# fuel_injectorREVB.net
KiCad netlist of a schematic drawn in EAGLE
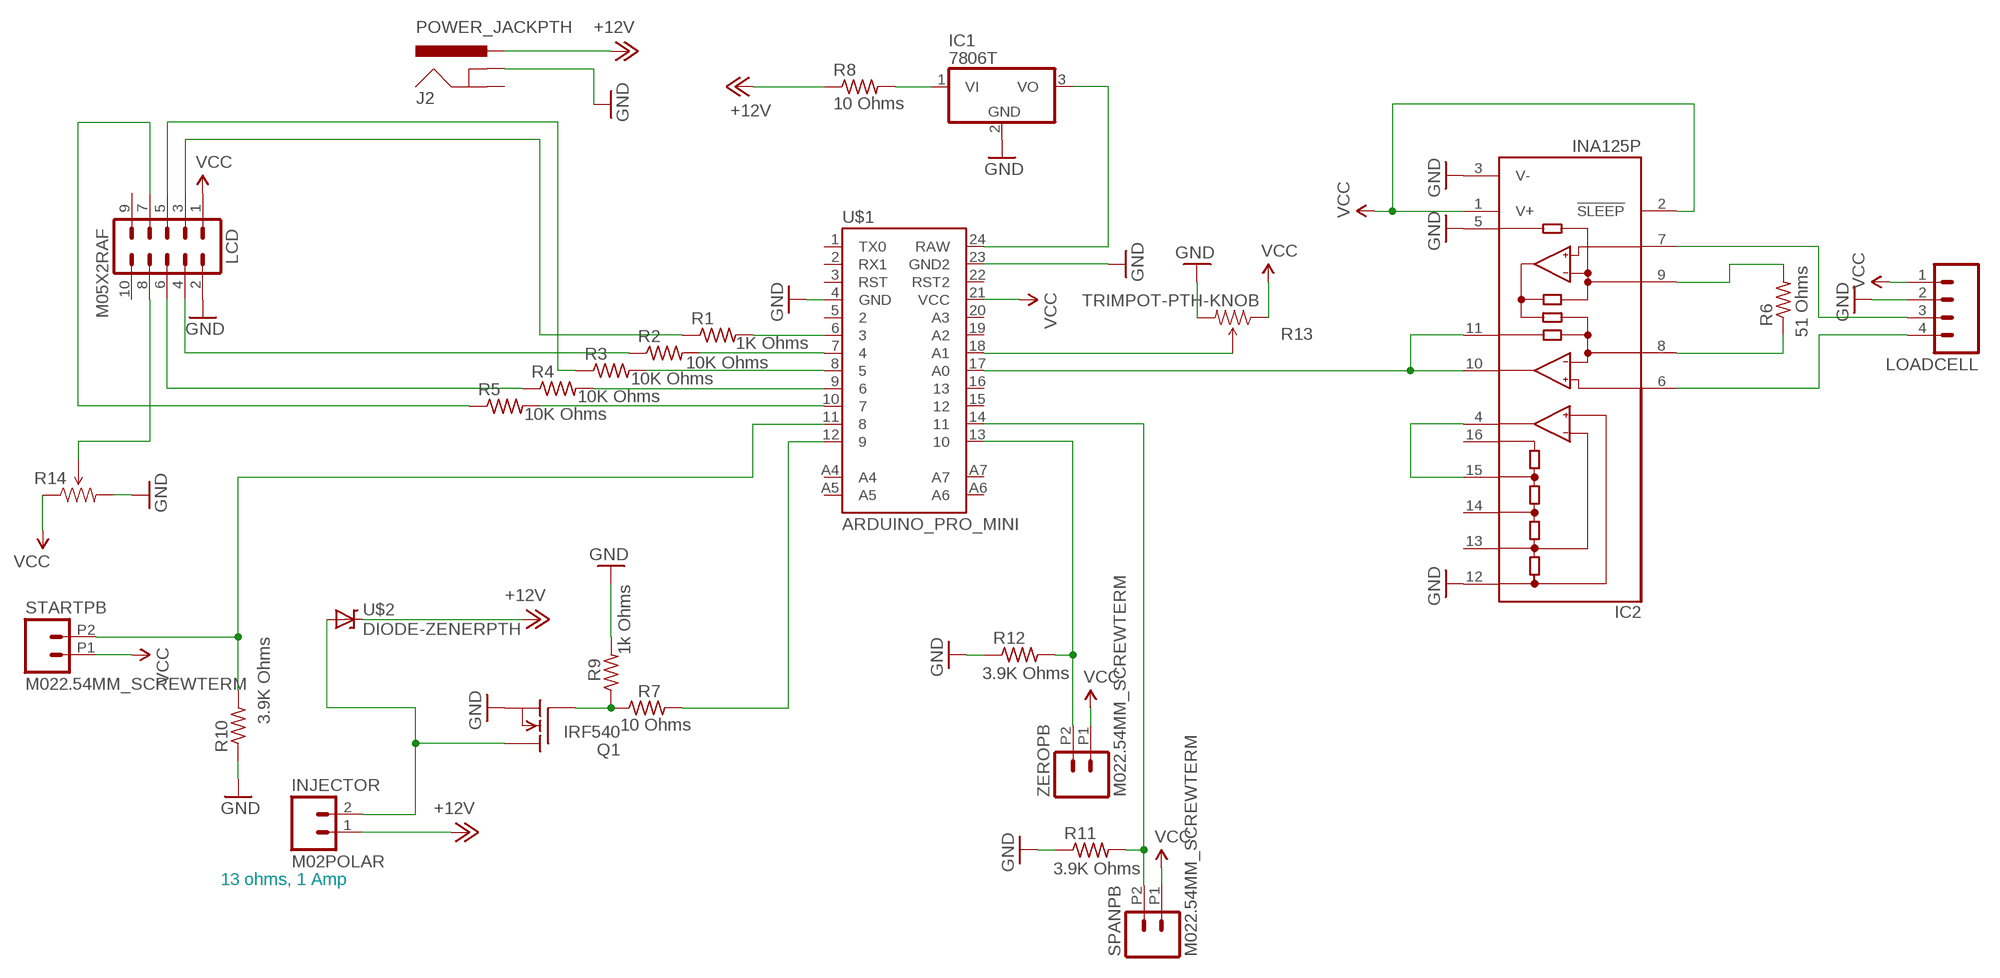
[diagram p0: schematic, sheet 1]

(export (version "E")
  (design (tool "Eeschema 10.0.6"))
  (components
    (comp (ref "IC1")
      (value "7806T")
      (footprint "eagle-import:TO220H")
      (libsource (lib "eagle-import") (part "78T06"))
    )
    (comp (ref "IC2")
      (value "INA125P")
      (footprint "eagle-import:DIL16")
      (fields (field (name "MF") "TEXAS INSTRUMENT CONNECTORS"))
      (libsource (lib "eagle-import") (part "INA125P"))
    )
    (comp (ref "INJECTOR")
      (value "M02POLAR")
      (footprint "eagle-import:MOLEX-1X2")
      (libsource (lib "eagle-import") (part "M02POLAR"))
    )
    (comp (ref "J2")
      (value "POWER_JACKPTH")
      (footprint "eagle-import:POWER_JACK_PTH")
      (libsource (lib "eagle-import") (part "POWER_JACKPTH"))
    )
    (comp (ref "LCD")
      (value "M05X2RAF")
      (footprint "eagle-import:2X5-RAF")
      (libsource (lib "eagle-import") (part "M05X2RAF"))
    )
    (comp (ref "LOADCELL")
      (value "M04POLAR")
      (footprint "eagle-import:MOLEX-1X4")
      (libsource (lib "eagle-import") (part "M04POLAR"))
    )
    (comp (ref "Q1")
      (value "IRF540")
      (footprint "eagle-import:TO220")
      (libsource (lib "eagle-import") (part "IRF540"))
    )
    (comp (ref "R1")
      (value "1K Ohms")
      (footprint "eagle-import:0309_10")
      (libsource (lib "eagle-import") (part "resistor_R-US_0309/10"))
    )
    (comp (ref "R2")
      (value "10K Ohms")
      (footprint "eagle-import:0309_10")
      (libsource (lib "eagle-import") (part "resistor_R-US_0309/10"))
    )
    (comp (ref "R3")
      (value "10K Ohms")
      (footprint "eagle-import:0309_10")
      (libsource (lib "eagle-import") (part "resistor_R-US_0309/10"))
    )
    (comp (ref "R4")
      (value "10K Ohms")
      (footprint "eagle-import:0309_10")
      (libsource (lib "eagle-import") (part "resistor_R-US_0309/10"))
    )
    (comp (ref "R5")
      (value "10K Ohms")
      (footprint "eagle-import:0309_10")
      (libsource (lib "eagle-import") (part "resistor_R-US_0309/10"))
    )
    (comp (ref "R6")
      (value "51 Ohms")
      (footprint "eagle-import:0309_10")
      (libsource (lib "eagle-import") (part "resistor_R-US_0309/10"))
    )
    (comp (ref "R7")
      (value "10 Ohms")
      (footprint "eagle-import:0207_15")
      (libsource (lib "eagle-import") (part "resistor_R-US_0207/15"))
    )
    (comp (ref "R8")
      (value "10 Ohms")
      (footprint "eagle-import:P0613_15")
      (libsource (lib "eagle-import") (part "R-US_0613/15"))
    )
    (comp (ref "R9")
      (value "1k Ohms")
      (footprint "eagle-import:0309_10")
      (libsource (lib "eagle-import") (part "resistor_R-US_0309/10"))
    )
    (comp (ref "R10")
      (value "3.9K Ohms")
      (footprint "eagle-import:0309_10")
      (libsource (lib "eagle-import") (part "resistor_R-US_0309/10"))
    )
    (comp (ref "R11")
      (value "3.9K Ohms")
      (footprint "eagle-import:0309_10")
      (libsource (lib "eagle-import") (part "resistor_R-US_0309/10"))
    )
    (comp (ref "R12")
      (value "3.9K Ohms")
      (footprint "eagle-import:0309_10")
      (libsource (lib "eagle-import") (part "resistor_R-US_0309/10"))
    )
    (comp (ref "R13")
      (value "TRIMPOT-PTH-KNOB")
      (footprint "eagle-import:3386U")
      (libsource (lib "eagle-import") (part "TRIMPOT-PTH-KNOB"))
    )
    (comp (ref "R14")
      (value "TRIMPOT-PTH-KNOB")
      (footprint "eagle-import:3386U")
      (libsource (lib "eagle-import") (part "TRIMPOT-PTH-KNOB"))
    )
    (comp (ref "SPANPB")
      (value "M022.54MM_SCREWTERM")
      (footprint "eagle-import:1X02_2.54_SCREWTERM")
      (libsource (lib "eagle-import") (part "M022.54MM_SCREWTERM"))
    )
    (comp (ref "STARTPB")
      (value "M022.54MM_SCREWTERM")
      (footprint "eagle-import:1X02_2.54_SCREWTERM")
      (libsource (lib "eagle-import") (part "M022.54MM_SCREWTERM"))
    )
    (comp (ref "U$1")
      (value "ARDUINO_PRO_MINI")
      (footprint "eagle-import:ARDUINO_PRO_MINI")
      (libsource (lib "eagle-import") (part "ARDUINO_PRO_MINI"))
    )
    (comp (ref "U$2")
      (value "DIODE-ZENERPTH")
      (footprint "eagle-import:DIODE-ZENER")
      (libsource (lib "eagle-import") (part "DIODE-ZENERPTH"))
    )
    (comp (ref "ZEROPB")
      (value "M022.54MM_SCREWTERM")
      (footprint "eagle-import:1X02_2.54_SCREWTERM")
      (libsource (lib "eagle-import") (part "M022.54MM_SCREWTERM"))
    )
  )
  (nets
    (net (code "1") (name "+12V") (class "Default")
      (node (ref "INJECTOR") (pin "1") (pinfunction "1_1") (pintype "passive"))
      (node (ref "J2") (pin "PWR") (pinfunction "PWR_PWR") (pintype "bidirectional"))
      (node (ref "R8") (pin "1") (pinfunction "1_1") (pintype "passive"))
      (node (ref "U$2") (pin "P$1") (pinfunction "C_P$1") (pintype "passive"))
    )
    (net (code "2") (name "GND") (class "Default")
      (node (ref "IC1") (pin "2") (pinfunction "GND_2") (pintype "passive"))
      (node (ref "IC2") (pin "12") (pinfunction "REFCOM_12") (pintype "passive"))
      (node (ref "IC2") (pin "3") (pinfunction "V-_3") (pintype "power_in"))
      (node (ref "IC2") (pin "5") (pinfunction "REF_5") (pintype "passive"))
      (node (ref "J2") (pin "GNDBREAK") (pinfunction "GNDBREAK_GNDBREAK") (pintype "bidirectional"))
      (node (ref "LCD") (pin "2") (pinfunction "2_2") (pintype "passive"))
      (node (ref "LOADCELL") (pin "2") (pinfunction "2_2") (pintype "passive"))
      (node (ref "Q1") (pin "3") (pinfunction "S_3") (pintype "passive"))
      (node (ref "R10") (pin "1") (pinfunction "1_1") (pintype "passive"))
      (node (ref "R11") (pin "1") (pinfunction "1_1") (pintype "passive"))
      (node (ref "R12") (pin "1") (pinfunction "1_1") (pintype "passive"))
      (node (ref "R13") (pin "3") (pinfunction "CW_3") (pintype "passive"))
      (node (ref "R14") (pin "3") (pinfunction "CW_3") (pintype "passive"))
      (node (ref "R9") (pin "2") (pinfunction "2_2") (pintype "passive"))
      (node (ref "U$1") (pin "23") (pinfunction "GND2_23") (pintype "bidirectional"))
      (node (ref "U$1") (pin "4") (pinfunction "GND_4") (pintype "bidirectional"))
    )
    (net (code "3") (name "Net-(IC1-VI)") (class "Default")
      (node (ref "IC1") (pin "1") (pinfunction "VI_1") (pintype "input"))
      (node (ref "R8") (pin "2") (pinfunction "2_2") (pintype "passive"))
    )
    (net (code "4") (name "Net-(IC1-VO)") (class "Default")
      (node (ref "IC1") (pin "3") (pinfunction "VO_3") (pintype "passive"))
      (node (ref "U$1") (pin "24") (pinfunction "RAW_24") (pintype "bidirectional"))
    )
    (net (code "5") (name "Net-(IC2-+IN)") (class "Default")
      (node (ref "IC2") (pin "6") (pinfunction "+IN_6") (pintype "input"))
      (node (ref "LOADCELL") (pin "4") (pinfunction "4_4") (pintype "passive"))
    )
    (net (code "6") (name "Net-(IC2--IN)") (class "Default")
      (node (ref "IC2") (pin "7") (pinfunction "-IN_7") (pintype "input"))
      (node (ref "LOADCELL") (pin "3") (pinfunction "3_3") (pintype "passive"))
    )
    (net (code "7") (name "Net-(IC2-OUT)") (class "Default")
      (node (ref "IC2") (pin "10") (pinfunction "OUT_10") (pintype "output"))
      (node (ref "IC2") (pin "11") (pinfunction "SENSE_11") (pintype "passive"))
      (node (ref "U$1") (pin "17") (pinfunction "A0_17") (pintype "bidirectional"))
    )
    (net (code "8") (name "Net-(IC2-REF5)") (class "Default")
      (node (ref "IC2") (pin "15") (pinfunction "REF5_15") (pintype "output"))
      (node (ref "IC2") (pin "4") (pinfunction "REFOUT_4") (pintype "output"))
    )
    (net (code "9") (name "Net-(IC2-RG-Pad8)") (class "Default")
      (node (ref "IC2") (pin "8") (pinfunction "RG_8") (pintype "passive"))
      (node (ref "R6") (pin "1") (pinfunction "1_1") (pintype "passive"))
    )
    (net (code "10") (name "Net-(IC2-RG-Pad9)") (class "Default")
      (node (ref "IC2") (pin "9") (pinfunction "RG_9") (pintype "passive"))
      (node (ref "R6") (pin "2") (pinfunction "2_2") (pintype "passive"))
    )
    (net (code "11") (name "Net-(LCD-Pad3)") (class "Default")
      (node (ref "LCD") (pin "3") (pinfunction "3_3") (pintype "passive"))
      (node (ref "R1") (pin "1") (pinfunction "1_1") (pintype "passive"))
    )
    (net (code "12") (name "Net-(LCD-Pad4)") (class "Default")
      (node (ref "LCD") (pin "4") (pinfunction "4_4") (pintype "passive"))
      (node (ref "R2") (pin "1") (pinfunction "1_1") (pintype "passive"))
    )
    (net (code "13") (name "Net-(LCD-Pad5)") (class "Default")
      (node (ref "LCD") (pin "5") (pinfunction "5_5") (pintype "passive"))
      (node (ref "R3") (pin "1") (pinfunction "1_1") (pintype "passive"))
    )
    (net (code "14") (name "Net-(LCD-Pad6)") (class "Default")
      (node (ref "LCD") (pin "6") (pinfunction "6_6") (pintype "passive"))
      (node (ref "R4") (pin "1") (pinfunction "1_1") (pintype "passive"))
    )
    (net (code "15") (name "Net-(LCD-Pad7)") (class "Default")
      (node (ref "LCD") (pin "7") (pinfunction "7_7") (pintype "passive"))
      (node (ref "R5") (pin "1") (pinfunction "1_1") (pintype "passive"))
    )
    (net (code "16") (name "Net-(Q1-D)") (class "Default")
      (node (ref "INJECTOR") (pin "2") (pinfunction "2_2") (pintype "passive"))
      (node (ref "Q1") (pin "2") (pinfunction "D_2") (pintype "passive"))
      (node (ref "U$2") (pin "P$2") (pinfunction "A_P$2") (pintype "passive"))
    )
    (net (code "17") (name "Net-(Q1-G)") (class "Default")
      (node (ref "Q1") (pin "1") (pinfunction "G_1") (pintype "passive"))
      (node (ref "R7") (pin "1") (pinfunction "1_1") (pintype "passive"))
      (node (ref "R9") (pin "1") (pinfunction "1_1") (pintype "passive"))
    )
    (net (code "18") (name "Net-(R13-WIPER)") (class "Default")
      (node (ref "R13") (pin "2") (pinfunction "WIPER_2") (pintype "passive"))
      (node (ref "U$1") (pin "18") (pinfunction "A1_18") (pintype "bidirectional"))
    )
    (net (code "19") (name "Net-(R14-WIPER)") (class "Default")
      (node (ref "LCD") (pin "8") (pinfunction "8_8") (pintype "passive"))
      (node (ref "R14") (pin "2") (pinfunction "WIPER_2") (pintype "passive"))
    )
    (net (code "20") (name "Net-(SPANPB-2)") (class "Default")
      (node (ref "R11") (pin "2") (pinfunction "2_2") (pintype "passive"))
      (node (ref "SPANPB") (pin "P2") (pinfunction "2_P2") (pintype "passive"))
      (node (ref "U$1") (pin "14") (pinfunction "11_14") (pintype "bidirectional"))
    )
    (net (code "21") (name "Net-(STARTPB-2)") (class "Default")
      (node (ref "R10") (pin "2") (pinfunction "2_2") (pintype "passive"))
      (node (ref "STARTPB") (pin "P2") (pinfunction "2_P2") (pintype "passive"))
      (node (ref "U$1") (pin "11") (pinfunction "8_11") (pintype "bidirectional"))
    )
    (net (code "22") (name "Net-(U$1-3)") (class "Default")
      (node (ref "R1") (pin "2") (pinfunction "2_2") (pintype "passive"))
      (node (ref "U$1") (pin "6") (pinfunction "3_6") (pintype "bidirectional"))
    )
    (net (code "23") (name "Net-(U$1-4)") (class "Default")
      (node (ref "R2") (pin "2") (pinfunction "2_2") (pintype "passive"))
      (node (ref "U$1") (pin "7") (pinfunction "4_7") (pintype "bidirectional"))
    )
    (net (code "24") (name "Net-(U$1-5)") (class "Default")
      (node (ref "R3") (pin "2") (pinfunction "2_2") (pintype "passive"))
      (node (ref "U$1") (pin "8") (pinfunction "5_8") (pintype "bidirectional"))
    )
    (net (code "25") (name "Net-(U$1-6)") (class "Default")
      (node (ref "R4") (pin "2") (pinfunction "2_2") (pintype "passive"))
      (node (ref "U$1") (pin "9") (pinfunction "6_9") (pintype "bidirectional"))
    )
    (net (code "26") (name "Net-(U$1-7)") (class "Default")
      (node (ref "R5") (pin "2") (pinfunction "2_2") (pintype "passive"))
      (node (ref "U$1") (pin "10") (pinfunction "7_10") (pintype "bidirectional"))
    )
    (net (code "27") (name "Net-(U$1-9)") (class "Default")
      (node (ref "R7") (pin "2") (pinfunction "2_2") (pintype "passive"))
      (node (ref "U$1") (pin "12") (pinfunction "9_12") (pintype "bidirectional"))
    )
    (net (code "28") (name "Net-(U$1-10)") (class "Default")
      (node (ref "R12") (pin "2") (pinfunction "2_2") (pintype "passive"))
      (node (ref "U$1") (pin "13") (pinfunction "10_13") (pintype "bidirectional"))
      (node (ref "ZEROPB") (pin "P2") (pinfunction "2_P2") (pintype "passive"))
    )
    (net (code "29") (name "VCC") (class "Default")
      (node (ref "IC2") (pin "1") (pinfunction "V+_1") (pintype "power_in"))
      (node (ref "IC2") (pin "2") (pinfunction "~{SLEEP}_2") (pintype "input"))
      (node (ref "LCD") (pin "1") (pinfunction "1_1") (pintype "passive"))
      (node (ref "LOADCELL") (pin "1") (pinfunction "1_1") (pintype "passive"))
      (node (ref "R13") (pin "1") (pinfunction "CCW_1") (pintype "passive"))
      (node (ref "R14") (pin "1") (pinfunction "CCW_1") (pintype "passive"))
      (node (ref "SPANPB") (pin "P1") (pinfunction "1_P1") (pintype "passive"))
      (node (ref "STARTPB") (pin "P1") (pinfunction "1_P1") (pintype "passive"))
      (node (ref "U$1") (pin "21") (pinfunction "VCC_21") (pintype "bidirectional"))
      (node (ref "ZEROPB") (pin "P1") (pinfunction "1_P1") (pintype "passive"))
    )
    (net (code "30") (name "unconnected-(IC2-REF2.5-Pad14)") (class "Default")
      (node (ref "IC2") (pin "14") (pinfunction "REF2.5_14") (pintype "output"))
    )
    (net (code "31") (name "unconnected-(IC2-REF10-Pad16)") (class "Default")
      (node (ref "IC2") (pin "16") (pinfunction "REF10_16") (pintype "output"))
    )
    (net (code "32") (name "unconnected-(IC2-REFBG-Pad13)") (class "Default")
      (node (ref "IC2") (pin "13") (pinfunction "REFBG_13") (pintype "output"))
    )
    (net (code "33") (name "unconnected-(J2-PadGND)") (class "Default")
      (node (ref "J2") (pin "GND") (pinfunction "GND_GND") (pintype "bidirectional"))
    )
    (net (code "34") (name "unconnected-(LCD-Pad9)") (class "Default")
      (node (ref "LCD") (pin "9") (pinfunction "9_9") (pintype "passive"))
    )
    (net (code "35") (name "unconnected-(LCD-Pad10)") (class "Default")
      (node (ref "LCD") (pin "10") (pinfunction "10_10") (pintype "passive"))
    )
    (net (code "36") (name "unconnected-(U$1-2-Pad5)") (class "Default")
      (node (ref "U$1") (pin "5") (pinfunction "2_5") (pintype "bidirectional"))
    )
    (net (code "37") (name "unconnected-(U$1-12-Pad15)") (class "Default")
      (node (ref "U$1") (pin "15") (pinfunction "12_15") (pintype "bidirectional"))
    )
    (net (code "38") (name "unconnected-(U$1-13-Pad16)") (class "Default")
      (node (ref "U$1") (pin "16") (pinfunction "13_16") (pintype "bidirectional"))
    )
    (net (code "39") (name "unconnected-(U$1-A2-Pad19)") (class "Default")
      (node (ref "U$1") (pin "19") (pinfunction "A2_19") (pintype "bidirectional"))
    )
    (net (code "40") (name "unconnected-(U$1-A3-Pad20)") (class "Default")
      (node (ref "U$1") (pin "20") (pinfunction "A3_20") (pintype "bidirectional"))
    )
    (net (code "41") (name "unconnected-(U$1-PadA4)") (class "Default")
      (node (ref "U$1") (pin "A4") (pinfunction "A4_A4") (pintype "bidirectional"))
    )
    (net (code "42") (name "unconnected-(U$1-PadA5)") (class "Default")
      (node (ref "U$1") (pin "A5") (pinfunction "A5_A5") (pintype "bidirectional"))
    )
    (net (code "43") (name "unconnected-(U$1-PadA6)") (class "Default")
      (node (ref "U$1") (pin "A6") (pinfunction "A6_A6") (pintype "bidirectional"))
    )
    (net (code "44") (name "unconnected-(U$1-PadA7)") (class "Default")
      (node (ref "U$1") (pin "A7") (pinfunction "A7_A7") (pintype "bidirectional"))
    )
    (net (code "45") (name "unconnected-(U$1-RST-Pad3)") (class "Default")
      (node (ref "U$1") (pin "3") (pinfunction "RST_3") (pintype "bidirectional"))
    )
    (net (code "46") (name "unconnected-(U$1-RST2-Pad22)") (class "Default")
      (node (ref "U$1") (pin "22") (pinfunction "RST2_22") (pintype "bidirectional"))
    )
    (net (code "47") (name "unconnected-(U$1-RX1-Pad2)") (class "Default")
      (node (ref "U$1") (pin "2") (pinfunction "RX1_2") (pintype "bidirectional"))
    )
    (net (code "48") (name "unconnected-(U$1-TX0-Pad1)") (class "Default")
      (node (ref "U$1") (pin "1") (pinfunction "TX0_1") (pintype "bidirectional"))
    )
  )
)
